# LEDBatterychargeIndicatorCircuit.net
KiCad netlist of a schematic drawn in EAGLE
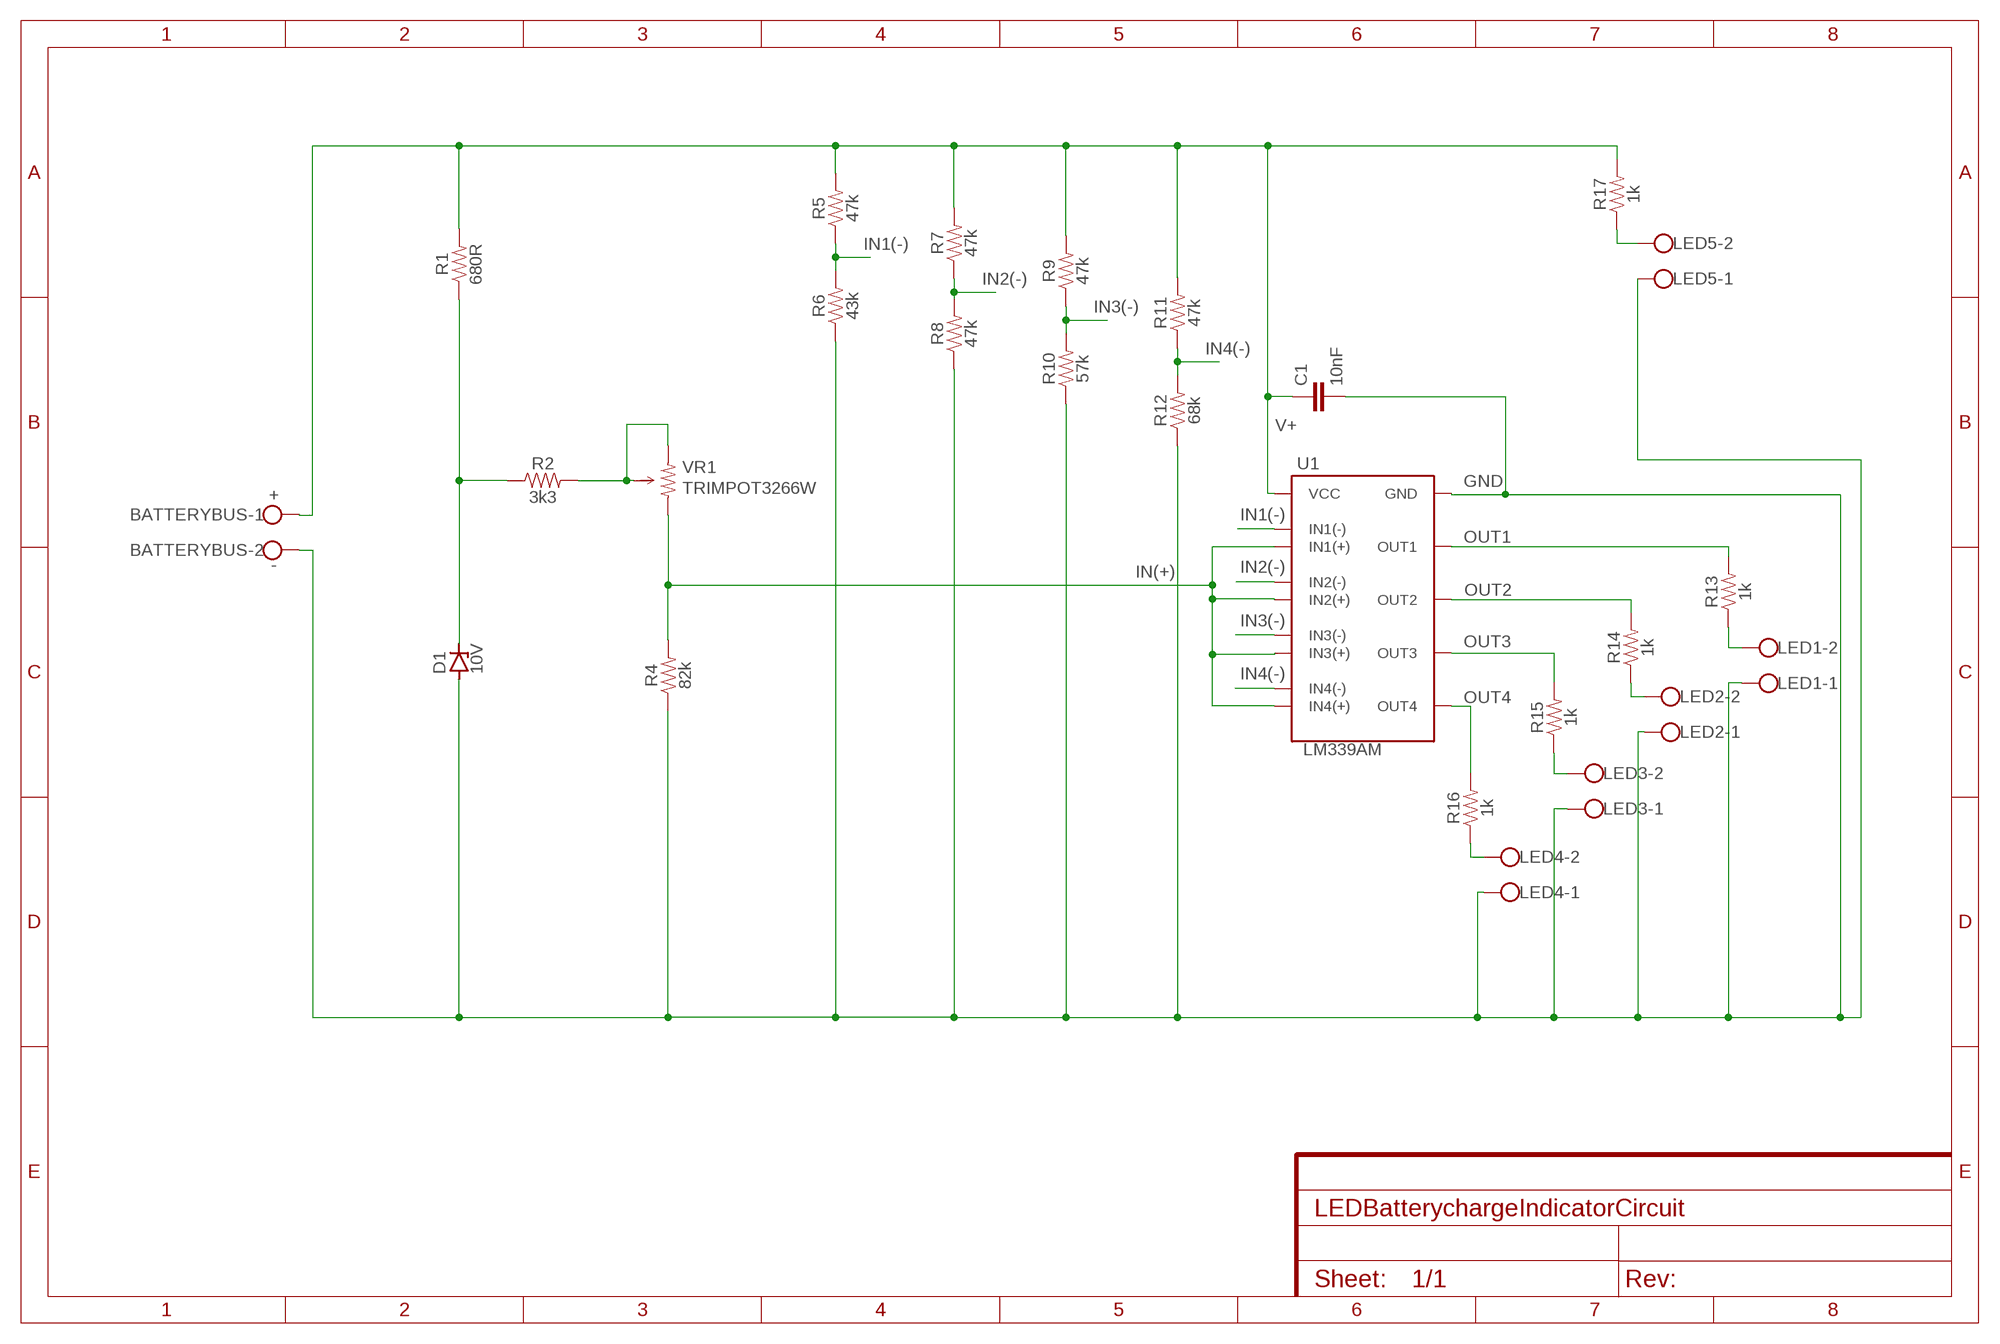
[diagram p0: schematic, sheet 1]

(export (version "E")
  (design (tool "Eeschema 10.0.6"))
  (components
    (comp (ref "BATTERYBUS")
      (value "W237-102")
      (footprint "eagle-import:W237-102")
      (fields (field (name "MPN") "237-102"))
      (libsource (lib "eagle-import") (part "W237-102"))
    )
    (comp (ref "C1")
      (value "10nF")
      (footprint "eagle-import:C7.5B5")
      (libsource (lib "eagle-import") (part "C7.5/5"))
    )
    (comp (ref "D1")
      (value "10V")
      (footprint "eagle-import:F126Z12")
      (libsource (lib "eagle-import") (part "ZENER-DIODEF126-12"))
    )
    (comp (ref "LED1")
      (value "W237-102")
      (footprint "eagle-import:W237-102")
      (fields (field (name "MPN") "237-102"))
      (libsource (lib "eagle-import") (part "W237-102"))
    )
    (comp (ref "LED2")
      (value "W237-102")
      (footprint "eagle-import:W237-102")
      (fields (field (name "MPN") "237-102"))
      (libsource (lib "eagle-import") (part "W237-102"))
    )
    (comp (ref "LED3")
      (value "W237-102")
      (footprint "eagle-import:W237-102")
      (fields (field (name "MPN") "237-102"))
      (libsource (lib "eagle-import") (part "W237-102"))
    )
    (comp (ref "LED4")
      (value "W237-102")
      (footprint "eagle-import:W237-102")
      (fields (field (name "MPN") "237-102"))
      (libsource (lib "eagle-import") (part "W237-102"))
    )
    (comp (ref "LED5")
      (value "W237-102")
      (footprint "eagle-import:W237-102")
      (fields (field (name "MPN") "237-102"))
      (libsource (lib "eagle-import") (part "W237-102"))
    )
    (comp (ref "R1")
      (value "680R")
      (footprint "eagle-import:0805")
      (libsource (lib "eagle-import") (part "RESISTOR0805"))
    )
    (comp (ref "R2")
      (value "3k3")
      (footprint "eagle-import:0805")
      (libsource (lib "eagle-import") (part "RESISTOR0805"))
    )
    (comp (ref "R4")
      (value "82k")
      (footprint "eagle-import:0805")
      (libsource (lib "eagle-import") (part "RESISTOR0805"))
    )
    (comp (ref "R5")
      (value "47k")
      (footprint "eagle-import:0805")
      (libsource (lib "eagle-import") (part "RESISTOR0805"))
    )
    (comp (ref "R6")
      (value "43k")
      (footprint "eagle-import:0805")
      (libsource (lib "eagle-import") (part "RESISTOR0805"))
    )
    (comp (ref "R7")
      (value "47k")
      (footprint "eagle-import:0805")
      (libsource (lib "eagle-import") (part "RESISTOR0805"))
    )
    (comp (ref "R8")
      (value "47k")
      (footprint "eagle-import:0805")
      (libsource (lib "eagle-import") (part "RESISTOR0805"))
    )
    (comp (ref "R9")
      (value "47k")
      (footprint "eagle-import:0805")
      (libsource (lib "eagle-import") (part "RESISTOR0805"))
    )
    (comp (ref "R10")
      (value "57k")
      (footprint "eagle-import:0805")
      (libsource (lib "eagle-import") (part "RESISTOR0805"))
    )
    (comp (ref "R11")
      (value "47k")
      (footprint "eagle-import:0805")
      (libsource (lib "eagle-import") (part "RESISTOR0805"))
    )
    (comp (ref "R12")
      (value "68k")
      (footprint "eagle-import:0805")
      (libsource (lib "eagle-import") (part "RESISTOR0805"))
    )
    (comp (ref "R13")
      (value "1k")
      (footprint "eagle-import:0805")
      (libsource (lib "eagle-import") (part "RESISTOR0805"))
    )
    (comp (ref "R14")
      (value "1k")
      (footprint "eagle-import:0805")
      (libsource (lib "eagle-import") (part "RESISTOR0805"))
    )
    (comp (ref "R15")
      (value "1k")
      (footprint "eagle-import:0805")
      (libsource (lib "eagle-import") (part "RESISTOR0805"))
    )
    (comp (ref "R16")
      (value "1k")
      (footprint "eagle-import:0805")
      (libsource (lib "eagle-import") (part "RESISTOR0805"))
    )
    (comp (ref "R17")
      (value "1k")
      (footprint "eagle-import:0805")
      (libsource (lib "eagle-import") (part "RESISTOR0805"))
    )
    (comp (ref "U1")
      (value "LM339AM")
      (footprint "eagle-import:LM339AM")
      (libsource (lib "eagle-import") (part "LM339AMSMD"))
    )
    (comp (ref "VR1")
      (value "TRIMPOT3266W")
      (footprint "eagle-import:TRIMPOT3266W")
      (libsource (lib "eagle-import") (part "TRIMPOT3266W"))
    )
  )
  (nets
    (net (code "1") (name "/GND") (class "Default")
      (node (ref "BATTERYBUS") (pin "2") (pinfunction "KL_2") (pintype "passive"))
      (node (ref "C1") (pin "2") (pinfunction "2_2") (pintype "passive"))
      (node (ref "D1") (pin "A") (pinfunction "A_A") (pintype "passive"))
      (node (ref "LED1") (pin "1") (pinfunction "KL_1") (pintype "passive"))
      (node (ref "LED2") (pin "1") (pinfunction "KL_1") (pintype "passive"))
      (node (ref "LED3") (pin "1") (pinfunction "KL_1") (pintype "passive"))
      (node (ref "LED4") (pin "1") (pinfunction "KL_1") (pintype "passive"))
      (node (ref "LED5") (pin "1") (pinfunction "KL_1") (pintype "passive"))
      (node (ref "R10") (pin "1") (pinfunction "1_1") (pintype "passive"))
      (node (ref "R12") (pin "1") (pinfunction "1_1") (pintype "passive"))
      (node (ref "R4") (pin "1") (pinfunction "1_1") (pintype "passive"))
      (node (ref "R6") (pin "1") (pinfunction "1_1") (pintype "passive"))
      (node (ref "R8") (pin "1") (pinfunction "1_1") (pintype "passive"))
      (node (ref "U1") (pin "12") (pinfunction "GND_12") (pintype "power_in"))
    )
    (net (code "2") (name "/IN(+)") (class "Default")
      (node (ref "R4") (pin "2") (pinfunction "2_2") (pintype "passive"))
      (node (ref "U1") (pin "11") (pinfunction "IN4(+)_11") (pintype "input"))
      (node (ref "U1") (pin "5") (pinfunction "IN1(+)_5") (pintype "input"))
      (node (ref "U1") (pin "7") (pinfunction "IN2(+)_7") (pintype "input"))
      (node (ref "U1") (pin "9") (pinfunction "IN3(+)_9") (pintype "input"))
      (node (ref "VR1") (pin "1") (pinfunction "1_1") (pintype "bidirectional"))
    )
    (net (code "3") (name "/IN1(-)") (class "Default")
      (node (ref "R5") (pin "1") (pinfunction "1_1") (pintype "passive"))
      (node (ref "R6") (pin "2") (pinfunction "2_2") (pintype "passive"))
      (node (ref "U1") (pin "4") (pinfunction "IN1(-)_4") (pintype "input"))
    )
    (net (code "4") (name "/IN2(-)") (class "Default")
      (node (ref "R7") (pin "1") (pinfunction "1_1") (pintype "passive"))
      (node (ref "R8") (pin "2") (pinfunction "2_2") (pintype "passive"))
      (node (ref "U1") (pin "6") (pinfunction "IN2(-)_6") (pintype "input"))
    )
    (net (code "5") (name "/IN3(-)") (class "Default")
      (node (ref "R10") (pin "2") (pinfunction "2_2") (pintype "passive"))
      (node (ref "R9") (pin "1") (pinfunction "1_1") (pintype "passive"))
      (node (ref "U1") (pin "8") (pinfunction "IN3(-)_8") (pintype "input"))
    )
    (net (code "6") (name "/IN4(-)") (class "Default")
      (node (ref "R11") (pin "1") (pinfunction "1_1") (pintype "passive"))
      (node (ref "R12") (pin "2") (pinfunction "2_2") (pintype "passive"))
      (node (ref "U1") (pin "10") (pinfunction "IN4(-)_10") (pintype "input"))
    )
    (net (code "7") (name "/OUT1") (class "Default")
      (node (ref "R13") (pin "2") (pinfunction "2_2") (pintype "passive"))
      (node (ref "U1") (pin "2") (pinfunction "OUT1_2") (pintype "output"))
    )
    (net (code "8") (name "/OUT2") (class "Default")
      (node (ref "R14") (pin "2") (pinfunction "2_2") (pintype "passive"))
      (node (ref "U1") (pin "1") (pinfunction "OUT2_1") (pintype "output"))
    )
    (net (code "9") (name "/OUT3") (class "Default")
      (node (ref "R15") (pin "2") (pinfunction "2_2") (pintype "passive"))
      (node (ref "U1") (pin "14") (pinfunction "OUT3_14") (pintype "output"))
    )
    (net (code "10") (name "/OUT4") (class "Default")
      (node (ref "R16") (pin "2") (pinfunction "2_2") (pintype "passive"))
      (node (ref "U1") (pin "13") (pinfunction "OUT4_13") (pintype "output"))
    )
    (net (code "11") (name "/V+") (class "Default")
      (node (ref "BATTERYBUS") (pin "1") (pinfunction "KL_1") (pintype "passive"))
      (node (ref "C1") (pin "1") (pinfunction "1_1") (pintype "passive"))
      (node (ref "R1") (pin "2") (pinfunction "2_2") (pintype "passive"))
      (node (ref "R11") (pin "2") (pinfunction "2_2") (pintype "passive"))
      (node (ref "R17") (pin "2") (pinfunction "2_2") (pintype "passive"))
      (node (ref "R5") (pin "2") (pinfunction "2_2") (pintype "passive"))
      (node (ref "R7") (pin "2") (pinfunction "2_2") (pintype "passive"))
      (node (ref "R9") (pin "2") (pinfunction "2_2") (pintype "passive"))
      (node (ref "U1") (pin "3") (pinfunction "VCC_3") (pintype "power_in"))
    )
    (net (code "12") (name "Net-(D1-PadC)") (class "Default")
      (node (ref "D1") (pin "C") (pinfunction "C_C") (pintype "passive"))
      (node (ref "R1") (pin "1") (pinfunction "1_1") (pintype "passive"))
      (node (ref "R2") (pin "1") (pinfunction "1_1") (pintype "passive"))
    )
    (net (code "13") (name "Net-(LED1B-KL)") (class "Default")
      (node (ref "LED1") (pin "2") (pinfunction "KL_2") (pintype "passive"))
      (node (ref "R13") (pin "1") (pinfunction "1_1") (pintype "passive"))
    )
    (net (code "14") (name "Net-(LED2B-KL)") (class "Default")
      (node (ref "LED2") (pin "2") (pinfunction "KL_2") (pintype "passive"))
      (node (ref "R14") (pin "1") (pinfunction "1_1") (pintype "passive"))
    )
    (net (code "15") (name "Net-(LED3B-KL)") (class "Default")
      (node (ref "LED3") (pin "2") (pinfunction "KL_2") (pintype "passive"))
      (node (ref "R15") (pin "1") (pinfunction "1_1") (pintype "passive"))
    )
    (net (code "16") (name "Net-(LED4B-KL)") (class "Default")
      (node (ref "LED4") (pin "2") (pinfunction "KL_2") (pintype "passive"))
      (node (ref "R16") (pin "1") (pinfunction "1_1") (pintype "passive"))
    )
    (net (code "17") (name "Net-(LED5B-KL)") (class "Default")
      (node (ref "LED5") (pin "2") (pinfunction "KL_2") (pintype "passive"))
      (node (ref "R17") (pin "1") (pinfunction "1_1") (pintype "passive"))
    )
    (net (code "18") (name "Net-(VR1-WIPER)") (class "Default")
      (node (ref "R2") (pin "2") (pinfunction "2_2") (pintype "passive"))
      (node (ref "VR1") (pin "2") (pinfunction "WIPER_2") (pintype "bidirectional"))
      (node (ref "VR1") (pin "3") (pinfunction "3_3") (pintype "bidirectional"))
    )
  )
)
